# LSD4RF_2F717N30_Interface.net
KiCad netlist of a schematic drawn in Altium Designer
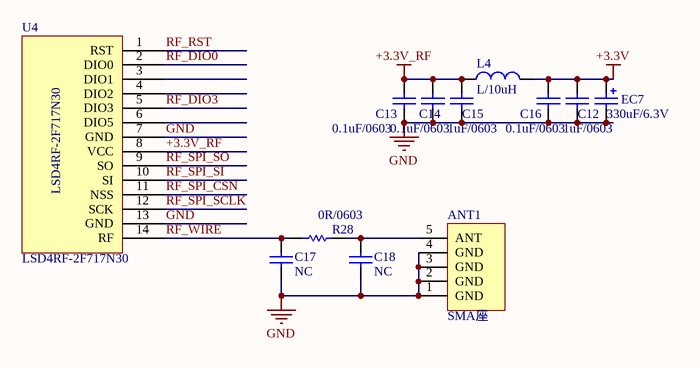
[diagram p0: LSD4RF_2F717N30_Interface.SchDoc]

(export (version "E")
  (design (tool "Eeschema 10.0.6"))
  (components
    (comp (ref "ANT1")
      (value "SMA座")
      (footprint "SMA")
      (libsource (lib "Menred_原理图 封装库") (part "OTHER/Antena/SMA座"))
    )
    (comp (ref "C12")
      (value "1uF/0603")
      (footprint "CAP/SMT/0603C")
      (libsource (lib "Menred_原理图 封装库") (part "CAP/CAP/SMT/0603C"))
    )
    (comp (ref "C13")
      (value "0.1uF/0603")
      (footprint "CAP/SMT/0603C")
      (libsource (lib "Menred_原理图 封装库") (part "CAP/CAP/SMT/0603C"))
    )
    (comp (ref "C14")
      (value "0.1uF/0603")
      (footprint "CAP/SMT/0603C")
      (libsource (lib "Menred_原理图 封装库") (part "CAP/CAP/SMT/0603C"))
    )
    (comp (ref "C15")
      (value "1uF/0603")
      (footprint "CAP/SMT/0603C")
      (libsource (lib "Menred_原理图 封装库") (part "CAP/CAP/SMT/0603C"))
    )
    (comp (ref "C16")
      (value "0.1uF/0603")
      (footprint "CAP/SMT/0603C")
      (libsource (lib "Menred_原理图 封装库") (part "CAP/CAP/SMT/0603C"))
    )
    (comp (ref "C17")
      (value "NC")
      (footprint "CAP/SMT/0603C")
      (libsource (lib "Menred_原理图 封装库") (part "CAP/CAP/SMT/0603C"))
    )
    (comp (ref "C18")
      (value "NC")
      (footprint "CAP/SMT/0603C")
      (libsource (lib "Menred_原理图 封装库") (part "CAP/CAP/SMT/0603C"))
    )
    (comp (ref "EC7")
      (value "330uF/6.3V")
      (footprint "CAP/SMT/330UF/6.3V")
      (libsource (lib "Menred_原理图 封装库") (part "CAP/AEC/SMT/330uF/6.3V"))
    )
    (comp (ref "L4")
      (value "L/10uH")
      (footprint "L/SMT/0603L")
      (libsource (lib "Menred_原理图 封装库") (part "L/BEAD/SMT/0603L"))
    )
    (comp (ref "R28")
      (value "0R/0603")
      (footprint "0603R")
      (libsource (lib "Menred_原理图 封装库") (part "RES/RES/SMT/0603"))
    )
    (comp (ref "U4")
      (value "LSD4RF-2F717N30")
      (footprint "MODEL/LSD4RF-2F717N30")
      (libsource (lib "集成模块") (part "MODLE/RF/LSD4RF-2F717N30"))
    )
  )
  (nets
    (net (code "1") (name "+3.3V") (class "Default")
      (node (ref "C12") (pin "2") (pinfunction "2_2") (pintype "passive"))
      (node (ref "C16") (pin "1") (pinfunction "1_1") (pintype "passive"))
      (node (ref "EC7") (pin "1") (pinfunction "1_1") (pintype "passive"))
      (node (ref "L4") (pin "2") (pinfunction "2_2") (pintype "passive"))
    )
    (net (code "2") (name "+3.3V_RF") (class "Default")
      (node (ref "C13") (pin "1") (pinfunction "1_1") (pintype "passive"))
      (node (ref "C14") (pin "1") (pinfunction "1_1") (pintype "passive"))
      (node (ref "C15") (pin "1") (pinfunction "1_1") (pintype "passive"))
      (node (ref "L4") (pin "1") (pinfunction "1_1") (pintype "passive"))
      (node (ref "U4") (pin "8") (pinfunction "VCC_8") (pintype "passive"))
    )
    (net (code "3") (name "/RF_DIO0") (class "Default")
      (node (ref "U4") (pin "2") (pinfunction "DIO0_2") (pintype "passive"))
    )
    (net (code "4") (name "/RF_DIO3") (class "Default")
      (node (ref "U4") (pin "5") (pinfunction "DIO3_5") (pintype "passive"))
    )
    (net (code "5") (name "/RF_RST") (class "Default")
      (node (ref "U4") (pin "1") (pinfunction "RST_1") (pintype "passive"))
    )
    (net (code "6") (name "/RF_SPI_CSN") (class "Default")
      (node (ref "U4") (pin "11") (pinfunction "NSS_11") (pintype "passive"))
    )
    (net (code "7") (name "/RF_SPI_SCLK") (class "Default")
      (node (ref "U4") (pin "12") (pinfunction "SCK_12") (pintype "passive"))
    )
    (net (code "8") (name "/RF_SPI_SI") (class "Default")
      (node (ref "U4") (pin "10") (pinfunction "SI_10") (pintype "passive"))
    )
    (net (code "9") (name "/RF_SPI_SO") (class "Default")
      (node (ref "U4") (pin "9") (pinfunction "SO_9") (pintype "passive"))
    )
    (net (code "10") (name "/RF_WIRE") (class "Default")
      (node (ref "C17") (pin "2") (pinfunction "2_2") (pintype "passive"))
      (node (ref "R28") (pin "1") (pinfunction "1_1") (pintype "passive"))
      (node (ref "U4") (pin "14") (pinfunction "RF_14") (pintype "passive"))
    )
    (net (code "11") (name "GND") (class "Default")
      (node (ref "ANT1") (pin "1") (pinfunction "GND_1") (pintype "passive"))
      (node (ref "ANT1") (pin "2") (pinfunction "GND_2") (pintype "passive"))
      (node (ref "ANT1") (pin "3") (pinfunction "GND_3") (pintype "passive"))
      (node (ref "ANT1") (pin "4") (pinfunction "GND_4") (pintype "passive"))
      (node (ref "C12") (pin "1") (pinfunction "1_1") (pintype "passive"))
      (node (ref "C13") (pin "2") (pinfunction "2_2") (pintype "passive"))
      (node (ref "C14") (pin "2") (pinfunction "2_2") (pintype "passive"))
      (node (ref "C15") (pin "2") (pinfunction "2_2") (pintype "passive"))
      (node (ref "C16") (pin "2") (pinfunction "2_2") (pintype "passive"))
      (node (ref "C17") (pin "1") (pinfunction "1_1") (pintype "passive"))
      (node (ref "C18") (pin "1") (pinfunction "1_1") (pintype "passive"))
      (node (ref "EC7") (pin "2") (pinfunction "2_2") (pintype "passive"))
      (node (ref "U4") (pin "13") (pinfunction "GND_13") (pintype "passive"))
      (node (ref "U4") (pin "7") (pinfunction "GND_7") (pintype "passive"))
    )
    (net (code "12") (name "Net-(ANT1-ANT)") (class "Default")
      (node (ref "ANT1") (pin "5") (pinfunction "ANT_5") (pintype "passive"))
      (node (ref "C18") (pin "2") (pinfunction "2_2") (pintype "passive"))
      (node (ref "R28") (pin "2") (pinfunction "2_2") (pintype "passive"))
    )
    (net (code "13") (name "unconnected-(U4-DIO1-Pad3)") (class "Default")
      (node (ref "U4") (pin "3") (pinfunction "DIO1_3") (pintype "passive"))
    )
    (net (code "14") (name "unconnected-(U4-DIO2-Pad4)") (class "Default")
      (node (ref "U4") (pin "4") (pinfunction "DIO2_4") (pintype "passive"))
    )
    (net (code "15") (name "unconnected-(U4-DIO5-Pad6)") (class "Default")
      (node (ref "U4") (pin "6") (pinfunction "DIO5_6") (pintype "passive"))
    )
  )
)
